# Power_Schematic.net
KiCad netlist of a schematic drawn in Altium Designer
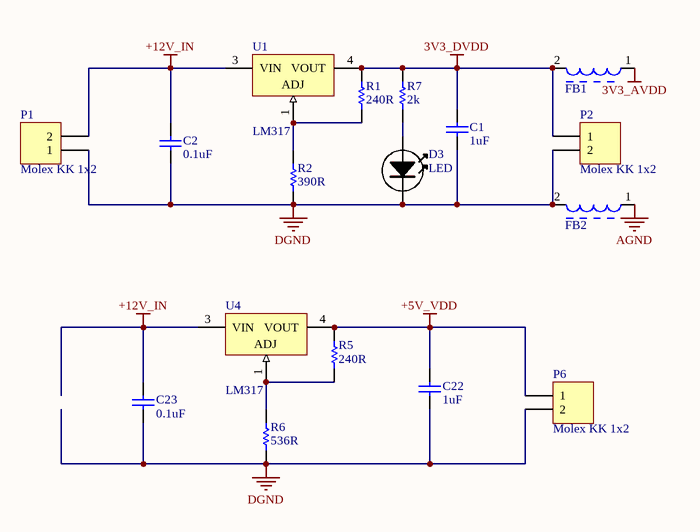
[diagram p0: Power_Schematic.SchDoc]

(export (version "E")
  (design (tool "Eeschema 10.0.6"))
  (components
    (comp (ref "C1")
      (value "1uF")
      (footprint "C0805")
      (description "0805 Capacitor")
      (libsource (lib "PARSEC") (part "C0805"))
    )
    (comp (ref "C2")
      (value "0.1uF")
      (footprint "C0805")
      (description "0805 Capacitor")
      (libsource (lib "PARSEC") (part "C0805"))
    )
    (comp (ref "C22")
      (value "1uF")
      (footprint "C0805")
      (description "0805 Capacitor")
      (libsource (lib "PARSEC") (part "C0805"))
    )
    (comp (ref "C23")
      (value "0.1uF")
      (footprint "C0805")
      (description "0805 Capacitor")
      (libsource (lib "PARSEC") (part "C0805"))
    )
    (comp (ref "D3")
      (value "LED")
      (footprint "0805LED")
      (fields
        (field (name "MANUFACTURER") "OSRAM Opto Semiconductors Inc")
        (field (name "MANUFACTURER PART NUMBER") "LS T676-Q1R2-1-Z")
      )
      (libsource (lib "PARSEC") (part "LED"))
    )
    (comp (ref "FB1")
      (value "FERRITE")
      (footprint "R0805")
      (description "FERRITE BEAD 0805")
      (libsource (lib "PARSEC") (part "FERRITE"))
    )
    (comp (ref "FB2")
      (value "FERRITE")
      (footprint "R0805")
      (description "FERRITE BEAD 0805")
      (libsource (lib "PARSEC") (part "FERRITE"))
    )
    (comp (ref "P1")
      (value "Molex KK 1x2")
      (footprint "Molex KK 2x1")
      (description "1x2 Molex KK Connector")
      (libsource (lib "") (part "Molex KK 1x2_1"))
    )
    (comp (ref "P2")
      (value "Molex KK 1x2")
      (footprint "Molex KK 2x1")
      (description "1x2 Molex KK Connector")
      (libsource (lib "PARSEC") (part "Molex KK 1x2"))
    )
    (comp (ref "P6")
      (value "Molex KK 1x2")
      (footprint "Molex KK 2x1")
      (description "1x2 Molex KK Connector")
      (libsource (lib "PARSEC") (part "Molex KK 1x2"))
    )
    (comp (ref "R1")
      (value "240R")
      (footprint "R0805")
      (description "RESISTOR 0805")
      (libsource (lib "PARSEC") (part "R0805"))
    )
    (comp (ref "R2")
      (value "390R")
      (footprint "R0805")
      (description "RESISTOR 0805")
      (libsource (lib "PARSEC") (part "R0805"))
    )
    (comp (ref "R5")
      (value "240R")
      (footprint "R0805")
      (description "RESISTOR 0805")
      (libsource (lib "PARSEC") (part "R0805"))
    )
    (comp (ref "R6")
      (value "536R")
      (footprint "R0805")
      (description "RESISTOR 0805")
      (libsource (lib "PARSEC") (part "R0805"))
    )
    (comp (ref "R7")
      (value "2k")
      (footprint "R0805")
      (description "RESISTOR 0805")
      (libsource (lib "PARSEC") (part "R0805"))
    )
    (comp (ref "U1")
      (value "LM317")
      (footprint "D-PAK")
      (description "Linear Voltage Regulator")
      (libsource (lib "PARSEC") (part "LM317"))
    )
    (comp (ref "U4")
      (value "LM317")
      (footprint "D-PAK")
      (description "Linear Voltage Regulator")
      (libsource (lib "PARSEC") (part "LM317"))
    )
  )
  (nets
    (net (code "1") (name "+5V_VDD") (class "Default")
      (node (ref "C22") (pin "1") (pinfunction "1_1") (pintype "passive"))
      (node (ref "P6") (pin "1") (pinfunction "1_1") (pintype "passive"))
      (node (ref "R5") (pin "2") (pinfunction "2_2") (pintype "passive"))
      (node (ref "U4") (pin "4") (pinfunction "VOUT_4") (pintype "power_in"))
    )
    (net (code "2") (name "+12V_IN") (class "Default")
      (node (ref "C2") (pin "1") (pinfunction "1_1") (pintype "passive"))
      (node (ref "C23") (pin "1") (pinfunction "1_1") (pintype "passive"))
      (node (ref "P1") (pin "2") (pinfunction "2_2") (pintype "passive"))
      (node (ref "U1") (pin "3") (pinfunction "VIN_3") (pintype "power_in"))
      (node (ref "U4") (pin "3") (pinfunction "VIN_3") (pintype "power_in"))
    )
    (net (code "3") (name "3V3_AVDD") (class "Default")
      (node (ref "FB1") (pin "1") (pinfunction "1_1") (pintype "passive"))
    )
    (net (code "4") (name "3V3_DVDD") (class "Default")
      (node (ref "C1") (pin "1") (pinfunction "1_1") (pintype "passive"))
      (node (ref "FB1") (pin "2") (pinfunction "2_2") (pintype "passive"))
      (node (ref "P2") (pin "1") (pinfunction "1_1") (pintype "passive"))
      (node (ref "R1") (pin "2") (pinfunction "2_2") (pintype "passive"))
      (node (ref "R7") (pin "2") (pinfunction "2_2") (pintype "passive"))
      (node (ref "U1") (pin "4") (pinfunction "VOUT_4") (pintype "power_in"))
    )
    (net (code "5") (name "AGND") (class "Default")
      (node (ref "FB2") (pin "1") (pinfunction "1_1") (pintype "passive"))
    )
    (net (code "6") (name "DGND") (class "Default")
      (node (ref "C1") (pin "2") (pinfunction "2_2") (pintype "passive"))
      (node (ref "C2") (pin "2") (pinfunction "2_2") (pintype "passive"))
      (node (ref "C22") (pin "2") (pinfunction "2_2") (pintype "passive"))
      (node (ref "C23") (pin "2") (pinfunction "2_2") (pintype "passive"))
      (node (ref "D3") (pin "K") (pintype "passive"))
      (node (ref "FB2") (pin "2") (pinfunction "2_2") (pintype "passive"))
      (node (ref "P1") (pin "1") (pinfunction "1_1") (pintype "passive"))
      (node (ref "P2") (pin "2") (pinfunction "2_2") (pintype "passive"))
      (node (ref "P6") (pin "2") (pinfunction "2_2") (pintype "passive"))
      (node (ref "R2") (pin "1") (pinfunction "1_1") (pintype "passive"))
      (node (ref "R6") (pin "1") (pinfunction "1_1") (pintype "passive"))
    )
    (net (code "7") (name "Net-(D3-PadA)") (class "Default")
      (node (ref "D3") (pin "A") (pintype "passive"))
      (node (ref "R7") (pin "1") (pinfunction "1_1") (pintype "passive"))
    )
    (net (code "8") (name "Net-(U1-ADJ)") (class "Default")
      (node (ref "R1") (pin "1") (pinfunction "1_1") (pintype "passive"))
      (node (ref "R2") (pin "2") (pinfunction "2_2") (pintype "passive"))
      (node (ref "U1") (pin "1") (pinfunction "ADJ_1") (pintype "input"))
    )
    (net (code "9") (name "Net-(U4-ADJ)") (class "Default")
      (node (ref "R5") (pin "1") (pinfunction "1_1") (pintype "passive"))
      (node (ref "R6") (pin "2") (pinfunction "2_2") (pintype "passive"))
      (node (ref "U4") (pin "1") (pinfunction "ADJ_1") (pintype "input"))
    )
  )
)
